# Microcontroller.net
KiCad netlist of a schematic drawn in Altium Designer
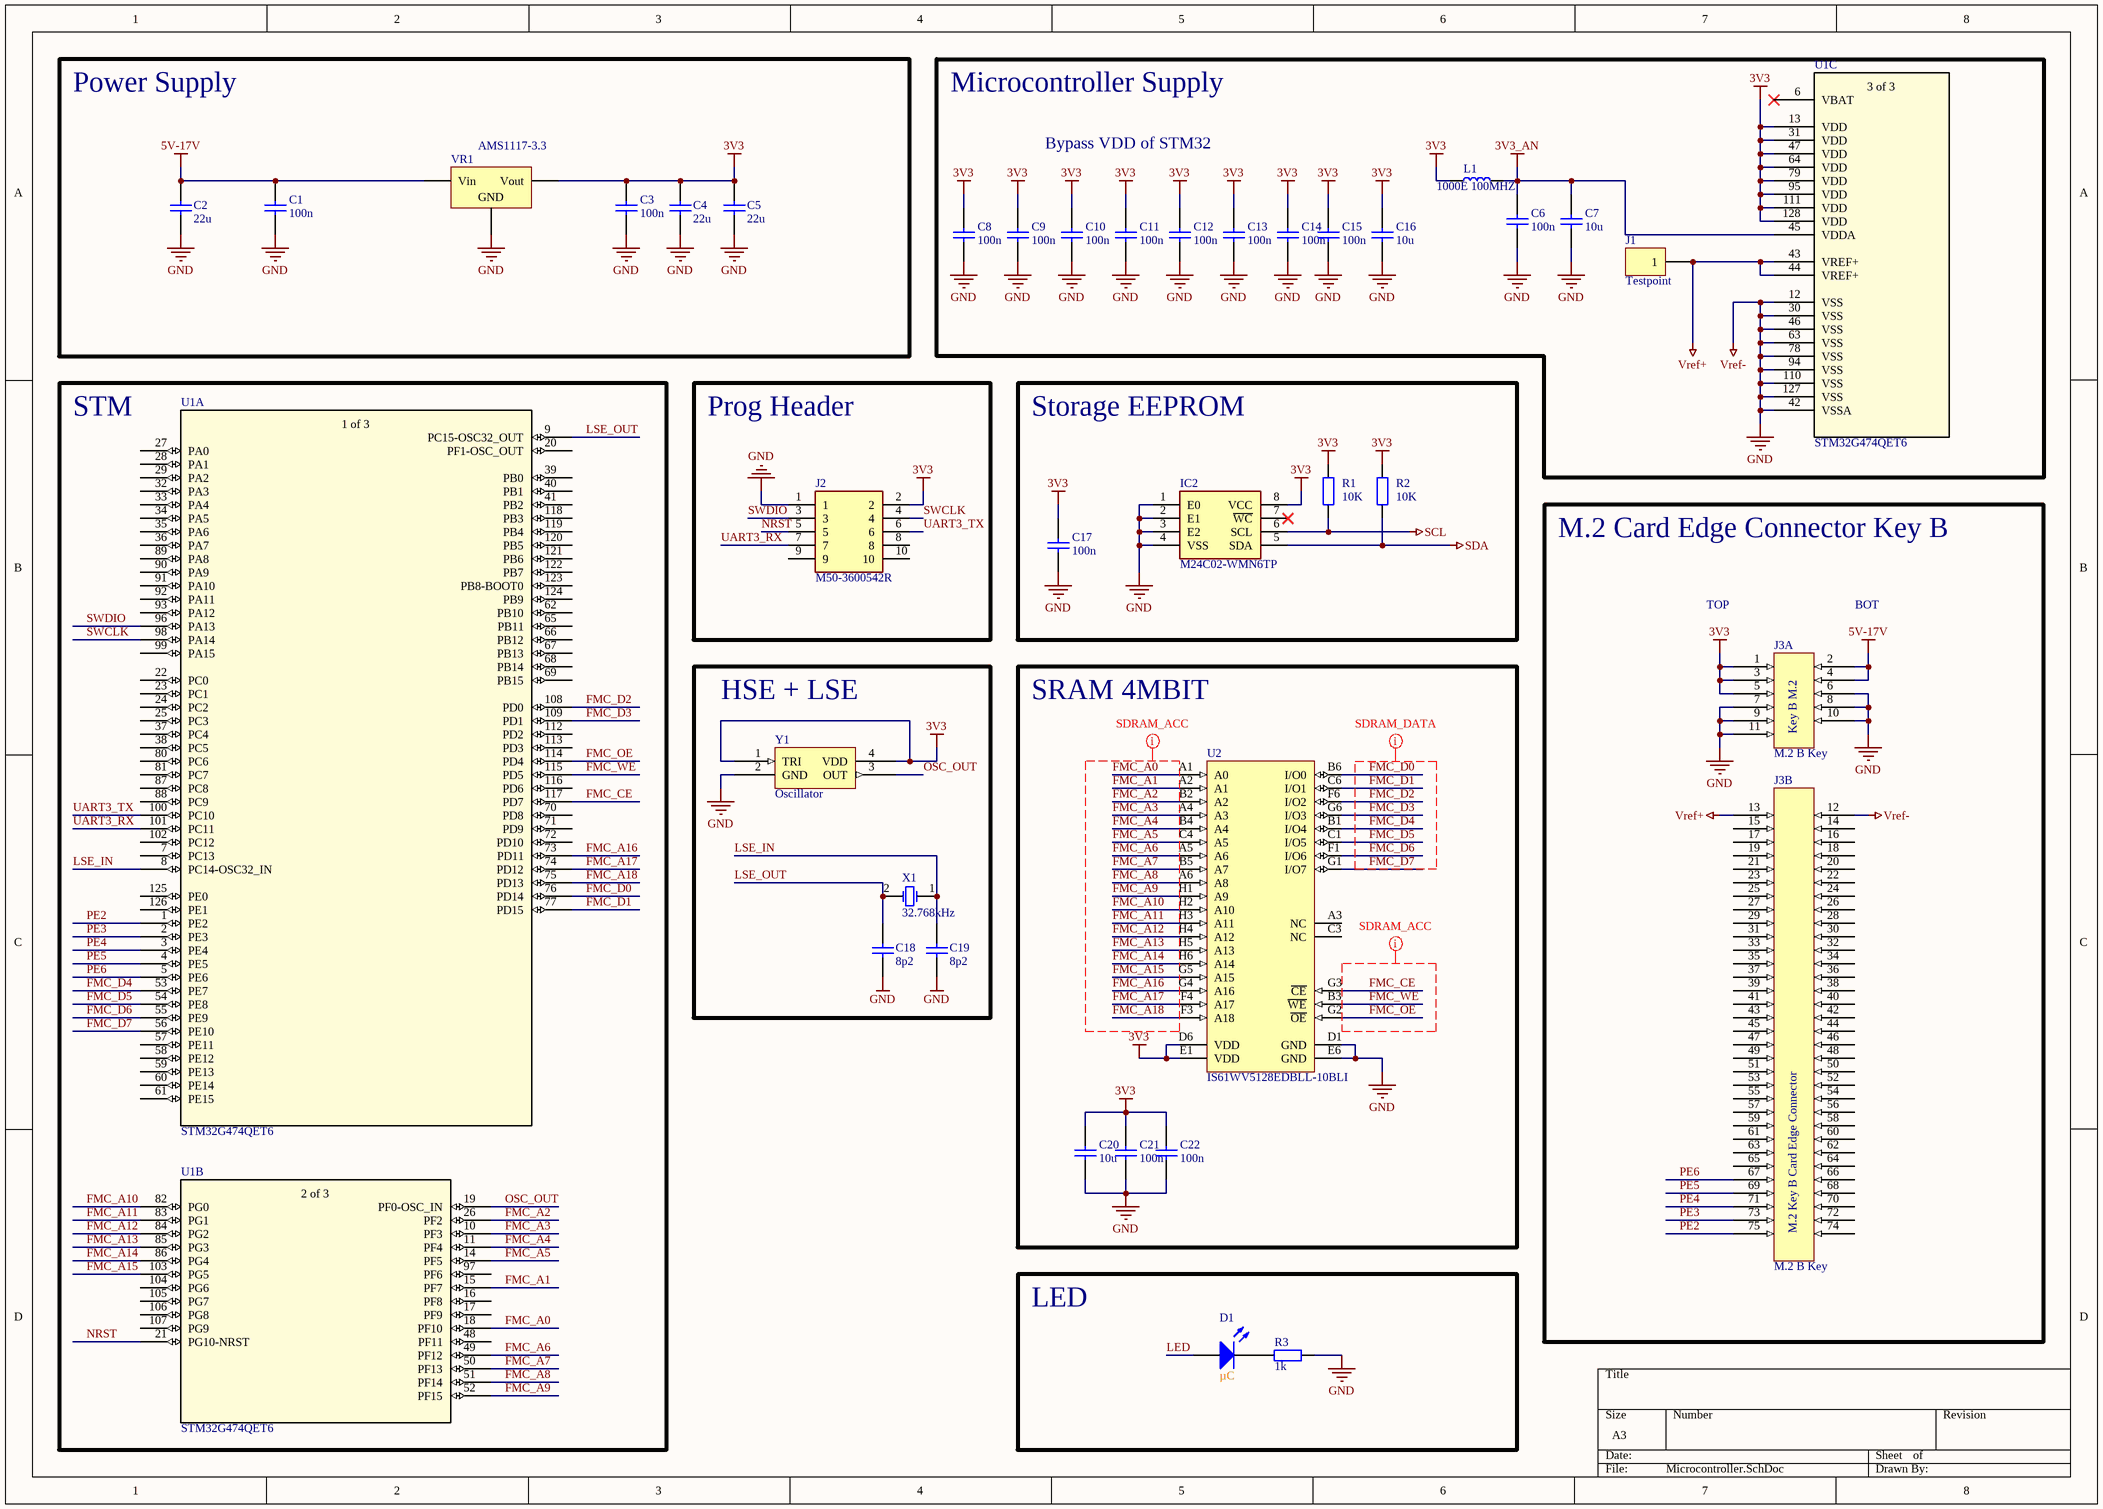
[diagram p0: Microcontroller.SchDoc]

(export (version "E")
  (design (tool "Eeschema 10.0.6"))
  (components
    (comp (ref "C1")
      (value "100n")
      (footprint "0402C")
      (description "Kondensator")
      (libsource (lib "WimLib") (part "Cap Ceramic"))
    )
    (comp (ref "C2")
      (value "22u")
      (footprint "1206C")
      (description "Kondensator")
      (libsource (lib "WimLib") (part "Cap Ceramic"))
    )
    (comp (ref "C3")
      (value "100n")
      (footprint "0402C")
      (description "Kondensator")
      (libsource (lib "WimLib") (part "Cap Ceramic"))
    )
    (comp (ref "C4")
      (value "22u")
      (footprint "1206C")
      (description "Kondensator")
      (libsource (lib "WimLib") (part "Cap Ceramic"))
    )
    (comp (ref "C5")
      (value "22u")
      (footprint "1206C")
      (description "Kondensator")
      (libsource (lib "WimLib") (part "Cap Ceramic"))
    )
    (comp (ref "C6")
      (value "100n")
      (footprint "0402C")
      (description "Kondensator")
      (libsource (lib "WimLib") (part "Cap Ceramic"))
    )
    (comp (ref "C7")
      (value "10u")
      (footprint "0603CH")
      (description "Kondensator")
      (libsource (lib "WimLib") (part "Cap Ceramic"))
    )
    (comp (ref "C8")
      (value "100n")
      (footprint "0402C")
      (description "Kondensator")
      (libsource (lib "WimLib") (part "Cap Ceramic"))
    )
    (comp (ref "C9")
      (value "100n")
      (footprint "0402C")
      (description "Kondensator")
      (libsource (lib "WimLib") (part "Cap Ceramic"))
    )
    (comp (ref "C10")
      (value "100n")
      (footprint "0402C")
      (description "Kondensator")
      (libsource (lib "WimLib") (part "Cap Ceramic"))
    )
    (comp (ref "C11")
      (value "100n")
      (footprint "0402C")
      (description "Kondensator")
      (libsource (lib "WimLib") (part "Cap Ceramic"))
    )
    (comp (ref "C12")
      (value "100n")
      (footprint "0402C")
      (description "Kondensator")
      (libsource (lib "WimLib") (part "Cap Ceramic"))
    )
    (comp (ref "C13")
      (value "100n")
      (footprint "0402C")
      (description "Kondensator")
      (libsource (lib "WimLib") (part "Cap Ceramic"))
    )
    (comp (ref "C14")
      (value "100n")
      (footprint "0402C")
      (description "Kondensator")
      (libsource (lib "WimLib") (part "Cap Ceramic"))
    )
    (comp (ref "C15")
      (value "100n")
      (footprint "0402C")
      (description "Kondensator")
      (libsource (lib "WimLib") (part "Cap Ceramic"))
    )
    (comp (ref "C16")
      (value "10u")
      (footprint "0603CH")
      (description "Kondensator")
      (libsource (lib "WimLib") (part "Cap Ceramic"))
    )
    (comp (ref "C17")
      (value "100n")
      (footprint "0402C")
      (description "Kondensator")
      (libsource (lib "WimLib") (part "Cap Ceramic"))
    )
    (comp (ref "C18")
      (value "8p2")
      (footprint "0402C")
      (description "Kondensator")
      (libsource (lib "WimLib") (part "Cap Ceramic"))
    )
    (comp (ref "C19")
      (value "8p2")
      (footprint "0402C")
      (description "Kondensator")
      (libsource (lib "WimLib") (part "Cap Ceramic"))
    )
    (comp (ref "C20")
      (value "10u")
      (footprint "0603CH")
      (description "Kondensator")
      (libsource (lib "WimLib") (part "Cap Ceramic"))
    )
    (comp (ref "C21")
      (value "100n")
      (footprint "0402C")
      (description "Kondensator")
      (libsource (lib "WimLib") (part "Cap Ceramic"))
    )
    (comp (ref "C22")
      (value "100n")
      (footprint "0402C")
      (description "Kondensator")
      (libsource (lib "WimLib") (part "Cap Ceramic"))
    )
    (comp (ref "D1")
      (value "µC")
      (footprint "1206_C")
      (description "Typical RED, GREEN, YELLOW, AMBER GaAs LED")
      (fields (field (name "PUBLISHER") "Altium Limited"))
      (libsource (lib "Miscellaneous Devices") (part "LED2"))
    )
    (comp (ref "IC2")
      (value "M24C02-WMN6TP")
      (footprint "SamacSys:SOIC127P600X175-8N")
      (description "Integrated Circuit")
      (fields (field (name "MOUSER PART NUMBER") "511-M24C02-WMN6TP"))
      (libsource (lib "SamacSys") (part "M24C02-WMN6TP"))
    )
    (comp (ref "J1")
      (value "Testpoint")
      (footprint "TESTPOINT")
      (description "Header, 1-Pin")
      (fields (field (name "PUBLISHER") "Altium Limited"))
      (libsource (lib "WimLibCon") (part "Header 1"))
    )
    (comp (ref "J2")
      (value "M50-3600542R")
      (footprint "SamacSys:HUSSP10W40P127_2X5_635X340X420P")
      (description "Connector")
      (fields (field (name "MOUSER PART NUMBER") "855-M50-3600542R"))
      (libsource (lib "*") (part "M50-3600542R"))
    )
    (comp (ref "J3")
      (value "M.2 B Key")
      (footprint "M.2 Key B")
      (libsource (lib "SimonLib") (part "M.2 B Key"))
    )
    (comp (ref "L1") (value "1000E 100MHZ") (footprint "0603L") (libsource (lib "WimLib") (part "Inductor")))
    (comp (ref "R1")
      (value "10K")
      (footprint "0402R")
      (description "Widerstand")
      (libsource (lib "WimLib") (part "Resistor"))
    )
    (comp (ref "R2")
      (value "10K")
      (footprint "0402R")
      (description "Widerstand")
      (libsource (lib "WimLib") (part "Resistor"))
    )
    (comp (ref "R3")
      (value "1k")
      (footprint "0402_R")
      (description "Resistor")
      (fields (field (name "Comment") "Res2") (field (name "PUBLISHER") "Altium Limited"))
      (libsource (lib "Miscellaneous Devices") (part "Res2"))
    )
    (comp (ref "U1")
      (value "STM32G474QET6")
      (footprint "LPQFP-128")
      (description "No Description Available")
      (libsource (lib "STM32G474QET6") (part "STM32G474QET6"))
    )
    (comp (ref "U2")
      (value "IS61WV5128EDBLL-10BLI")
      (footprint "ISSI-TF-BGA-36-6000x8000DE")
      (fields (field (name "MANUFACTURER") "Integrated Silicon Solution Inc (ISSI)"))
      (libsource (lib "Altium Content Vault") (part "ISSI-IS61WV5128EDBLL-TF-BGA-36"))
    )
    (comp (ref "VR1")
      (value "AMS1117-3.3")
      (footprint "SOT-223")
      (description "低压差线性稳压(LDO)")
      (libsource (lib "LDO") (part "SOT-223 AMS1117-3.3"))
    )
    (comp (ref "X1")
      (value "32.768kHz")
      (footprint "XTAL32768")
      (description "Crystal Oscillator")
      (fields (field (name "PUBLISHER") "Altium Limited"))
      (libsource (lib "WimLib") (part "XTAL"))
    )
    (comp (ref "Y1")
      (value "Oscillator")
      (footprint "Crystal SMD3225")
      (libsource (lib "SimonLib") (part "Oscillator"))
    )
  )
  (nets
    (net (code "1") (name "/FMC_A0") (class "Default")
      (node (ref "U1") (pin "18") (pinfunction "PF10_18") (pintype "bidirectional"))
      (node (ref "U2") (pin "A1") (pinfunction "A0_A1") (pintype "input"))
    )
    (net (code "2") (name "/FMC_A1") (class "Default")
      (node (ref "U1") (pin "15") (pinfunction "PF7_15") (pintype "bidirectional"))
      (node (ref "U2") (pin "A2") (pinfunction "A1_A2") (pintype "input"))
    )
    (net (code "3") (name "/FMC_A2") (class "Default")
      (node (ref "U1") (pin "26") (pinfunction "PF2_26") (pintype "bidirectional"))
      (node (ref "U2") (pin "B2") (pinfunction "A2_B2") (pintype "input"))
    )
    (net (code "4") (name "/FMC_A3") (class "Default")
      (node (ref "U1") (pin "10") (pinfunction "PF3_10") (pintype "bidirectional"))
      (node (ref "U2") (pin "A4") (pinfunction "A3_A4") (pintype "input"))
    )
    (net (code "5") (name "/FMC_A4") (class "Default")
      (node (ref "U1") (pin "11") (pinfunction "PF4_11") (pintype "bidirectional"))
      (node (ref "U2") (pin "B4") (pinfunction "A4_B4") (pintype "input"))
    )
    (net (code "6") (name "/FMC_A5") (class "Default")
      (node (ref "U1") (pin "14") (pinfunction "PF5_14") (pintype "bidirectional"))
      (node (ref "U2") (pin "C4") (pinfunction "A5_C4") (pintype "input"))
    )
    (net (code "7") (name "/FMC_A6") (class "Default")
      (node (ref "U1") (pin "49") (pinfunction "PF12_49") (pintype "bidirectional"))
      (node (ref "U2") (pin "A5") (pinfunction "A6_A5") (pintype "input"))
    )
    (net (code "8") (name "/FMC_A7") (class "Default")
      (node (ref "U1") (pin "50") (pinfunction "PF13_50") (pintype "bidirectional"))
      (node (ref "U2") (pin "B5") (pinfunction "A7_B5") (pintype "input"))
    )
    (net (code "9") (name "/FMC_A8") (class "Default")
      (node (ref "U1") (pin "51") (pinfunction "PF14_51") (pintype "bidirectional"))
      (node (ref "U2") (pin "A6") (pinfunction "A8_A6") (pintype "input"))
    )
    (net (code "10") (name "/FMC_A9") (class "Default")
      (node (ref "U1") (pin "52") (pinfunction "PF15_52") (pintype "bidirectional"))
      (node (ref "U2") (pin "H1") (pinfunction "A9_H1") (pintype "input"))
    )
    (net (code "11") (name "/FMC_A10") (class "Default")
      (node (ref "U1") (pin "82") (pinfunction "PG0_82") (pintype "bidirectional"))
      (node (ref "U2") (pin "H2") (pinfunction "A10_H2") (pintype "input"))
    )
    (net (code "12") (name "/FMC_A11") (class "Default")
      (node (ref "U1") (pin "83") (pinfunction "PG1_83") (pintype "bidirectional"))
      (node (ref "U2") (pin "H3") (pinfunction "A11_H3") (pintype "input"))
    )
    (net (code "13") (name "/FMC_A12") (class "Default")
      (node (ref "U1") (pin "84") (pinfunction "PG2_84") (pintype "bidirectional"))
      (node (ref "U2") (pin "H4") (pinfunction "A12_H4") (pintype "input"))
    )
    (net (code "14") (name "/FMC_A13") (class "Default")
      (node (ref "U1") (pin "85") (pinfunction "PG3_85") (pintype "bidirectional"))
      (node (ref "U2") (pin "H5") (pinfunction "A13_H5") (pintype "input"))
    )
    (net (code "15") (name "/FMC_A14") (class "Default")
      (node (ref "U1") (pin "86") (pinfunction "PG4_86") (pintype "bidirectional"))
      (node (ref "U2") (pin "H6") (pinfunction "A14_H6") (pintype "input"))
    )
    (net (code "16") (name "/FMC_A15") (class "Default")
      (node (ref "U1") (pin "103") (pinfunction "PG5_103") (pintype "bidirectional"))
      (node (ref "U2") (pin "G5") (pinfunction "A15_G5") (pintype "input"))
    )
    (net (code "17") (name "/FMC_A16") (class "Default")
      (node (ref "U1") (pin "73") (pinfunction "PD11_73") (pintype "bidirectional"))
      (node (ref "U2") (pin "G4") (pinfunction "A16_G4") (pintype "input"))
    )
    (net (code "18") (name "/FMC_A17") (class "Default")
      (node (ref "U1") (pin "74") (pinfunction "PD12_74") (pintype "bidirectional"))
      (node (ref "U2") (pin "F4") (pinfunction "A17_F4") (pintype "input"))
    )
    (net (code "19") (name "/FMC_A18") (class "Default")
      (node (ref "U1") (pin "75") (pinfunction "PD13_75") (pintype "bidirectional"))
      (node (ref "U2") (pin "F3") (pinfunction "A18_F3") (pintype "input"))
    )
    (net (code "20") (name "/FMC_CE") (class "Default")
      (node (ref "U1") (pin "117") (pinfunction "PD7_117") (pintype "bidirectional"))
      (node (ref "U2") (pin "G3") (pinfunction "~{CE}_G3") (pintype "input"))
    )
    (net (code "21") (name "/FMC_D0") (class "Default")
      (node (ref "U1") (pin "76") (pinfunction "PD14_76") (pintype "bidirectional"))
      (node (ref "U2") (pin "B6") (pinfunction "I/O0_B6") (pintype "bidirectional"))
    )
    (net (code "22") (name "/FMC_D1") (class "Default")
      (node (ref "U1") (pin "77") (pinfunction "PD15_77") (pintype "bidirectional"))
      (node (ref "U2") (pin "C6") (pinfunction "I/O1_C6") (pintype "bidirectional"))
    )
    (net (code "23") (name "/FMC_D2") (class "Default")
      (node (ref "U1") (pin "108") (pinfunction "PD0_108") (pintype "bidirectional"))
      (node (ref "U2") (pin "F6") (pinfunction "I/O2_F6") (pintype "bidirectional"))
    )
    (net (code "24") (name "/FMC_D3") (class "Default")
      (node (ref "U1") (pin "109") (pinfunction "PD1_109") (pintype "bidirectional"))
      (node (ref "U2") (pin "G6") (pinfunction "I/O3_G6") (pintype "bidirectional"))
    )
    (net (code "25") (name "/FMC_D4") (class "Default")
      (node (ref "U1") (pin "53") (pinfunction "PE7_53") (pintype "bidirectional"))
      (node (ref "U2") (pin "B1") (pinfunction "I/O4_B1") (pintype "bidirectional"))
    )
    (net (code "26") (name "/FMC_D5") (class "Default")
      (node (ref "U1") (pin "54") (pinfunction "PE8_54") (pintype "bidirectional"))
      (node (ref "U2") (pin "C1") (pinfunction "I/O5_C1") (pintype "bidirectional"))
    )
    (net (code "27") (name "/FMC_D6") (class "Default")
      (node (ref "U1") (pin "55") (pinfunction "PE9_55") (pintype "bidirectional"))
      (node (ref "U2") (pin "F1") (pinfunction "I/O6_F1") (pintype "bidirectional"))
    )
    (net (code "28") (name "/FMC_D7") (class "Default")
      (node (ref "U1") (pin "56") (pinfunction "PE10_56") (pintype "bidirectional"))
      (node (ref "U2") (pin "G1") (pinfunction "I/O7_G1") (pintype "bidirectional"))
    )
    (net (code "29") (name "/FMC_OE") (class "Default")
      (node (ref "U1") (pin "114") (pinfunction "PD4_114") (pintype "bidirectional"))
      (node (ref "U2") (pin "G2") (pinfunction "~{OE}_G2") (pintype "input"))
    )
    (net (code "30") (name "/FMC_WE") (class "Default")
      (node (ref "U1") (pin "115") (pinfunction "PD5_115") (pintype "bidirectional"))
      (node (ref "U2") (pin "B3") (pinfunction "~{WE}_B3") (pintype "input"))
    )
    (net (code "31") (name "/LED") (class "Default")
      (node (ref "D1") (pin "1") (pinfunction "A_1") (pintype "passive"))
    )
    (net (code "32") (name "/LSE_IN") (class "Default")
      (node (ref "C19") (pin "2") (pinfunction "2_2") (pintype "passive"))
      (node (ref "U1") (pin "8") (pinfunction "PC14-OSC32_IN_8") (pintype "bidirectional"))
      (node (ref "X1") (pin "1") (pinfunction "OSC1_1") (pintype "passive"))
    )
    (net (code "33") (name "/LSE_OUT") (class "Default")
      (node (ref "C18") (pin "2") (pinfunction "2_2") (pintype "passive"))
      (node (ref "U1") (pin "9") (pinfunction "PC15-OSC32_OUT_9") (pintype "bidirectional"))
      (node (ref "X1") (pin "2") (pinfunction "OSC2_2") (pintype "passive"))
    )
    (net (code "34") (name "/NRST") (class "Default")
      (node (ref "J2") (pin "5") (pinfunction "5_5") (pintype "passive"))
      (node (ref "U1") (pin "21") (pinfunction "PG10-NRST_21") (pintype "bidirectional"))
    )
    (net (code "35") (name "/OSC_OUT") (class "Default")
      (node (ref "U1") (pin "19") (pinfunction "PF0-OSC_IN_19") (pintype "bidirectional"))
      (node (ref "Y1") (pin "3") (pinfunction "OUT_3") (pintype "output"))
    )
    (net (code "36") (name "/PE2") (class "Default")
      (node (ref "J3") (pin "75") (pintype "input"))
      (node (ref "U1") (pin "1") (pinfunction "PE2_1") (pintype "bidirectional"))
    )
    (net (code "37") (name "/PE3") (class "Default")
      (node (ref "J3") (pin "73") (pintype "input"))
      (node (ref "U1") (pin "2") (pinfunction "PE3_2") (pintype "bidirectional"))
    )
    (net (code "38") (name "/PE4") (class "Default")
      (node (ref "J3") (pin "71") (pintype "input"))
      (node (ref "U1") (pin "3") (pinfunction "PE4_3") (pintype "bidirectional"))
    )
    (net (code "39") (name "/PE5") (class "Default")
      (node (ref "J3") (pin "69") (pintype "input"))
      (node (ref "U1") (pin "4") (pinfunction "PE5_4") (pintype "bidirectional"))
    )
    (net (code "40") (name "/PE6") (class "Default")
      (node (ref "J3") (pin "67") (pintype "input"))
      (node (ref "U1") (pin "5") (pinfunction "PE6_5") (pintype "bidirectional"))
    )
    (net (code "41") (name "/SWCLK") (class "Default")
      (node (ref "J2") (pin "4") (pinfunction "4_4") (pintype "passive"))
      (node (ref "U1") (pin "98") (pinfunction "PA14_98") (pintype "bidirectional"))
    )
    (net (code "42") (name "/SWDIO") (class "Default")
      (node (ref "J2") (pin "3") (pinfunction "3_3") (pintype "passive"))
      (node (ref "U1") (pin "96") (pinfunction "PA13_96") (pintype "bidirectional"))
    )
    (net (code "43") (name "/UART3_RX") (class "Default")
      (node (ref "J2") (pin "7") (pinfunction "7_7") (pintype "passive"))
      (node (ref "U1") (pin "101") (pinfunction "PC11_101") (pintype "bidirectional"))
    )
    (net (code "44") (name "/UART3_TX") (class "Default")
      (node (ref "J2") (pin "6") (pinfunction "6_6") (pintype "passive"))
      (node (ref "U1") (pin "100") (pinfunction "PC10_100") (pintype "bidirectional"))
    )
    (net (code "45") (name "3V3") (class "Default")
      (node (ref "C10") (pin "2") (pinfunction "2_2") (pintype "passive"))
      (node (ref "C11") (pin "2") (pinfunction "2_2") (pintype "passive"))
      (node (ref "C12") (pin "2") (pinfunction "2_2") (pintype "passive"))
      (node (ref "C13") (pin "2") (pinfunction "2_2") (pintype "passive"))
      (node (ref "C14") (pin "2") (pinfunction "2_2") (pintype "passive"))
      (node (ref "C15") (pin "2") (pinfunction "2_2") (pintype "passive"))
      (node (ref "C16") (pin "1") (pinfunction "1_1") (pintype "passive"))
      (node (ref "C17") (pin "2") (pinfunction "2_2") (pintype "passive"))
      (node (ref "C20") (pin "1") (pinfunction "1_1") (pintype "passive"))
      (node (ref "C21") (pin "2") (pinfunction "2_2") (pintype "passive"))
      (node (ref "C22") (pin "2") (pinfunction "2_2") (pintype "passive"))
      (node (ref "C3") (pin "2") (pinfunction "2_2") (pintype "passive"))
      (node (ref "C4") (pin "2") (pinfunction "2_2") (pintype "passive"))
      (node (ref "C5") (pin "2") (pinfunction "2_2") (pintype "passive"))
      (node (ref "C8") (pin "2") (pinfunction "2_2") (pintype "passive"))
      (node (ref "C9") (pin "2") (pinfunction "2_2") (pintype "passive"))
      (node (ref "IC2") (pin "8") (pinfunction "VCC_8") (pintype "passive"))
      (node (ref "J2") (pin "2") (pinfunction "2_2") (pintype "passive"))
      (node (ref "J3") (pin "1") (pintype "input"))
      (node (ref "J3") (pin "3") (pintype "input"))
      (node (ref "J3") (pin "5") (pintype "input"))
      (node (ref "L1") (pin "1") (pinfunction "1_1") (pintype "passive"))
      (node (ref "R1") (pin "1") (pinfunction "1_1") (pintype "passive"))
      (node (ref "R2") (pin "1") (pinfunction "1_1") (pintype "passive"))
      (node (ref "U1") (pin "111") (pinfunction "VDD_111") (pintype "power_in"))
      (node (ref "U1") (pin "128") (pinfunction "VDD_128") (pintype "power_in"))
      (node (ref "U1") (pin "13") (pinfunction "VDD_13") (pintype "power_in"))
      (node (ref "U1") (pin "31") (pinfunction "VDD_31") (pintype "power_in"))
      (node (ref "U1") (pin "47") (pinfunction "VDD_47") (pintype "power_in"))
      (node (ref "U1") (pin "64") (pinfunction "VDD_64") (pintype "power_in"))
      (node (ref "U1") (pin "79") (pinfunction "VDD_79") (pintype "power_in"))
      (node (ref "U1") (pin "95") (pinfunction "VDD_95") (pintype "power_in"))
      (node (ref "U2") (pin "D6") (pinfunction "VDD_D6") (pintype "power_in"))
      (node (ref "U2") (pin "E1") (pinfunction "VDD_E1") (pintype "power_in"))
      (node (ref "VR1") (pin "2") (pinfunction "Vout_2") (pintype "passive"))
      (node (ref "Y1") (pin "1") (pinfunction "TRI_1") (pintype "input"))
      (node (ref "Y1") (pin "4") (pinfunction "VDD_4") (pintype "power_in"))
    )
    (net (code "46") (name "3V3_AN") (class "Default")
      (node (ref "C6") (pin "2") (pinfunction "2_2") (pintype "passive"))
      (node (ref "C7") (pin "1") (pinfunction "1_1") (pintype "passive"))
      (node (ref "L1") (pin "2") (pinfunction "2_2") (pintype "passive"))
      (node (ref "U1") (pin "45") (pinfunction "VDDA_45") (pintype "power_in"))
    )
    (net (code "47") (name "5V-17V") (class "Default")
      (node (ref "C1") (pin "2") (pinfunction "2_2") (pintype "passive"))
      (node (ref "C2") (pin "2") (pinfunction "2_2") (pintype "passive"))
      (node (ref "J3") (pin "2") (pintype "input"))
      (node (ref "J3") (pin "4") (pintype "input"))
      (node (ref "VR1") (pin "3") (pinfunction "Vin_3") (pintype "passive"))
    )
    (net (code "48") (name "GND") (class "Default")
      (node (ref "C1") (pin "1") (pinfunction "1_1") (pintype "passive"))
      (node (ref "C10") (pin "1") (pinfunction "1_1") (pintype "passive"))
      (node (ref "C11") (pin "1") (pinfunction "1_1") (pintype "passive"))
      (node (ref "C12") (pin "1") (pinfunction "1_1") (pintype "passive"))
      (node (ref "C13") (pin "1") (pinfunction "1_1") (pintype "passive"))
      (node (ref "C14") (pin "1") (pinfunction "1_1") (pintype "passive"))
      (node (ref "C15") (pin "1") (pinfunction "1_1") (pintype "passive"))
      (node (ref "C16") (pin "2") (pinfunction "2_2") (pintype "passive"))
      (node (ref "C17") (pin "1") (pinfunction "1_1") (pintype "passive"))
      (node (ref "C18") (pin "1") (pinfunction "1_1") (pintype "passive"))
      (node (ref "C19") (pin "1") (pinfunction "1_1") (pintype "passive"))
      (node (ref "C2") (pin "1") (pinfunction "1_1") (pintype "passive"))
      (node (ref "C20") (pin "2") (pinfunction "2_2") (pintype "passive"))
      (node (ref "C21") (pin "1") (pinfunction "1_1") (pintype "passive"))
      (node (ref "C22") (pin "1") (pinfunction "1_1") (pintype "passive"))
      (node (ref "C3") (pin "1") (pinfunction "1_1") (pintype "passive"))
      (node (ref "C4") (pin "1") (pinfunction "1_1") (pintype "passive"))
      (node (ref "C5") (pin "1") (pinfunction "1_1") (pintype "passive"))
      (node (ref "C6") (pin "1") (pinfunction "1_1") (pintype "passive"))
      (node (ref "C7") (pin "2") (pinfunction "2_2") (pintype "passive"))
      (node (ref "C8") (pin "1") (pinfunction "1_1") (pintype "passive"))
      (node (ref "C9") (pin "1") (pinfunction "1_1") (pintype "passive"))
      (node (ref "IC2") (pin "1") (pinfunction "E0_1") (pintype "passive"))
      (node (ref "IC2") (pin "2") (pinfunction "E1_2") (pintype "passive"))
      (node (ref "IC2") (pin "3") (pinfunction "E2_3") (pintype "passive"))
      (node (ref "IC2") (pin "4") (pinfunction "VSS_4") (pintype "passive"))
      (node (ref "J2") (pin "1") (pinfunction "1_1") (pintype "passive"))
      (node (ref "J3") (pin "10") (pintype "input"))
      (node (ref "J3") (pin "11") (pintype "input"))
      (node (ref "J3") (pin "12") (pintype "input"))
      (node (ref "J3") (pin "6") (pintype "input"))
      (node (ref "J3") (pin "7") (pintype "input"))
      (node (ref "J3") (pin "8") (pintype "input"))
      (node (ref "J3") (pin "9") (pintype "input"))
      (node (ref "R3") (pin "1") (pinfunction "1_1") (pintype "passive"))
      (node (ref "U1") (pin "110") (pinfunction "VSS_110") (pintype "power_in"))
      (node (ref "U1") (pin "12") (pinfunction "VSS_12") (pintype "power_in"))
      (node (ref "U1") (pin "127") (pinfunction "VSS_127") (pintype "power_in"))
      (node (ref "U1") (pin "30") (pinfunction "VSS_30") (pintype "power_in"))
      (node (ref "U1") (pin "42") (pinfunction "VSSA_42") (pintype "power_in"))
      (node (ref "U1") (pin "46") (pinfunction "VSS_46") (pintype "power_in"))
      (node (ref "U1") (pin "63") (pinfunction "VSS_63") (pintype "power_in"))
      (node (ref "U1") (pin "78") (pinfunction "VSS_78") (pintype "power_in"))
      (node (ref "U1") (pin "94") (pinfunction "VSS_94") (pintype "power_in"))
      (node (ref "U2") (pin "D1") (pinfunction "GND_D1") (pintype "power_in"))
      (node (ref "U2") (pin "E6") (pinfunction "GND_E6") (pintype "power_in"))
      (node (ref "VR1") (pin "1") (pinfunction "GND_1") (pintype "passive"))
      (node (ref "Y1") (pin "2") (pinfunction "GND_2") (pintype "power_in"))
    )
    (net (code "49") (name "Net-(D1-K)") (class "Default")
      (node (ref "D1") (pin "2") (pinfunction "K_2") (pintype "passive"))
      (node (ref "R3") (pin "2") (pinfunction "2_2") (pintype "passive"))
    )
    (net (code "50") (name "SCL") (class "Default")
      (node (ref "IC2") (pin "6") (pinfunction "SCL_6") (pintype "passive"))
      (node (ref "R1") (pin "2") (pinfunction "2_2") (pintype "passive"))
    )
    (net (code "51") (name "SDA") (class "Default")
      (node (ref "IC2") (pin "5") (pinfunction "SDA_5") (pintype "passive"))
      (node (ref "R2") (pin "2") (pinfunction "2_2") (pintype "passive"))
    )
    (net (code "52") (name "Vref+") (class "Default")
      (node (ref "J1") (pin "1") (pinfunction "1_1") (pintype "passive"))
      (node (ref "J3") (pin "13") (pintype "input"))
      (node (ref "U1") (pin "43") (pinfunction "VREF+_43") (pintype "power_in"))
      (node (ref "U1") (pin "44") (pinfunction "VREF+_44") (pintype "power_in"))
    )
    (net (code "53") (name "unconnected-(IC2-~{WC}-Pad7)") (class "Default")
      (node (ref "IC2") (pin "7") (pinfunction "~{WC}_7") (pintype "passive+no_connect"))
    )
    (net (code "54") (name "unconnected-(J2-Pad8)") (class "Default")
      (node (ref "J2") (pin "8") (pinfunction "8_8") (pintype "passive"))
    )
    (net (code "55") (name "unconnected-(J2-Pad9)") (class "Default")
      (node (ref "J2") (pin "9") (pinfunction "9_9") (pintype "passive"))
    )
    (net (code "56") (name "unconnected-(J2-Pad10)") (class "Default")
      (node (ref "J2") (pin "10") (pinfunction "10_10") (pintype "passive"))
    )
    (net (code "57") (name "unconnected-(J3-Pad14)") (class "Default")
      (node (ref "J3") (pin "14") (pintype "input"))
    )
    (net (code "58") (name "unconnected-(J3-Pad15)") (class "Default")
      (node (ref "J3") (pin "15") (pintype "input"))
    )
    (net (code "59") (name "unconnected-(J3-Pad16)") (class "Default")
      (node (ref "J3") (pin "16") (pintype "input"))
    )
    (net (code "60") (name "unconnected-(J3-Pad17)") (class "Default")
      (node (ref "J3") (pin "17") (pintype "input"))
    )
    (net (code "61") (name "unconnected-(J3-Pad18)") (class "Default")
      (node (ref "J3") (pin "18") (pintype "input"))
    )
    (net (code "62") (name "unconnected-(J3-Pad19)") (class "Default")
      (node (ref "J3") (pin "19") (pintype "input"))
    )
    (net (code "63") (name "unconnected-(J3-Pad20)") (class "Default")
      (node (ref "J3") (pin "20") (pintype "input"))
    )
    (net (code "64") (name "unconnected-(J3-Pad21)") (class "Default")
      (node (ref "J3") (pin "21") (pintype "input"))
    )
    (net (code "65") (name "unconnected-(J3-Pad22)") (class "Default")
      (node (ref "J3") (pin "22") (pintype "input"))
    )
    (net (code "66") (name "unconnected-(J3-Pad23)") (class "Default")
      (node (ref "J3") (pin "23") (pintype "input"))
    )
    (net (code "67") (name "unconnected-(J3-Pad24)") (class "Default")
      (node (ref "J3") (pin "24") (pintype "input"))
    )
    (net (code "68") (name "unconnected-(J3-Pad25)") (class "Default")
      (node (ref "J3") (pin "25") (pintype "input"))
    )
    (net (code "69") (name "unconnected-(J3-Pad26)") (class "Default")
      (node (ref "J3") (pin "26") (pintype "input"))
    )
    (net (code "70") (name "unconnected-(J3-Pad27)") (class "Default")
      (node (ref "J3") (pin "27") (pintype "input"))
    )
    (net (code "71") (name "unconnected-(J3-Pad28)") (class "Default")
      (node (ref "J3") (pin "28") (pintype "input"))
    )
    (net (code "72") (name "unconnected-(J3-Pad29)") (class "Default")
      (node (ref "J3") (pin "29") (pintype "input"))
    )
    (net (code "73") (name "unconnected-(J3-Pad30)") (class "Default")
      (node (ref "J3") (pin "30") (pintype "input"))
    )
    (net (code "74") (name "unconnected-(J3-Pad31)") (class "Default")
      (node (ref "J3") (pin "31") (pintype "input"))
    )
    (net (code "75") (name "unconnected-(J3-Pad32)") (class "Default")
      (node (ref "J3") (pin "32") (pintype "input"))
    )
    (net (code "76") (name "unconnected-(J3-Pad33)") (class "Default")
      (node (ref "J3") (pin "33") (pintype "input"))
    )
    (net (code "77") (name "unconnected-(J3-Pad34)") (class "Default")
      (node (ref "J3") (pin "34") (pintype "input"))
    )
    (net (code "78") (name "unconnected-(J3-Pad35)") (class "Default")
      (node (ref "J3") (pin "35") (pintype "input"))
    )
    (net (code "79") (name "unconnected-(J3-Pad36)") (class "Default")
      (node (ref "J3") (pin "36") (pintype "input"))
    )
    (net (code "80") (name "unconnected-(J3-Pad37)") (class "Default")
      (node (ref "J3") (pin "37") (pintype "input"))
    )
    (net (code "81") (name "unconnected-(J3-Pad38)") (class "Default")
      (node (ref "J3") (pin "38") (pintype "input"))
    )
    (net (code "82") (name "unconnected-(J3-Pad39)") (class "Default")
      (node (ref "J3") (pin "39") (pintype "input"))
    )
    (net (code "83") (name "unconnected-(J3-Pad40)") (class "Default")
      (node (ref "J3") (pin "40") (pintype "input"))
    )
    (net (code "84") (name "unconnected-(J3-Pad41)") (class "Default")
      (node (ref "J3") (pin "41") (pintype "input"))
    )
    (net (code "85") (name "unconnected-(J3-Pad42)") (class "Default")
      (node (ref "J3") (pin "42") (pintype "input"))
    )
    (net (code "86") (name "unconnected-(J3-Pad43)") (class "Default")
      (node (ref "J3") (pin "43") (pintype "input"))
    )
    (net (code "87") (name "unconnected-(J3-Pad44)") (class "Default")
      (node (ref "J3") (pin "44") (pintype "input"))
    )
    (net (code "88") (name "unconnected-(J3-Pad45)") (class "Default")
      (node (ref "J3") (pin "45") (pintype "input"))
    )
    (net (code "89") (name "unconnected-(J3-Pad46)") (class "Default")
      (node (ref "J3") (pin "46") (pintype "input"))
    )
    (net (code "90") (name "unconnected-(J3-Pad47)") (class "Default")
      (node (ref "J3") (pin "47") (pintype "input"))
    )
    (net (code "91") (name "unconnected-(J3-Pad48)") (class "Default")
      (node (ref "J3") (pin "48") (pintype "input"))
    )
    (net (code "92") (name "unconnected-(J3-Pad49)") (class "Default")
      (node (ref "J3") (pin "49") (pintype "input"))
    )
    (net (code "93") (name "unconnected-(J3-Pad50)") (class "Default")
      (node (ref "J3") (pin "50") (pintype "input"))
    )
    (net (code "94") (name "unconnected-(J3-Pad51)") (class "Default")
      (node (ref "J3") (pin "51") (pintype "input"))
    )
    (net (code "95") (name "unconnected-(J3-Pad52)") (class "Default")
      (node (ref "J3") (pin "52") (pintype "input"))
    )
    (net (code "96") (name "unconnected-(J3-Pad53)") (class "Default")
      (node (ref "J3") (pin "53") (pintype "input"))
    )
    (net (code "97") (name "unconnected-(J3-Pad54)") (class "Default")
      (node (ref "J3") (pin "54") (pintype "input"))
    )
    (net (code "98") (name "unconnected-(J3-Pad55)") (class "Default")
      (node (ref "J3") (pin "55") (pintype "input"))
    )
    (net (code "99") (name "unconnected-(J3-Pad56)") (class "Default")
      (node (ref "J3") (pin "56") (pintype "input"))
    )
    (net (code "100") (name "unconnected-(J3-Pad57)") (class "Default")
      (node (ref "J3") (pin "57") (pintype "input"))
    )
    (net (code "101") (name "unconnected-(J3-Pad58)") (class "Default")
      (node (ref "J3") (pin "58") (pintype "input"))
    )
    (net (code "102") (name "unconnected-(J3-Pad59)") (class "Default")
      (node (ref "J3") (pin "59") (pintype "input"))
    )
    (net (code "103") (name "unconnected-(J3-Pad60)") (class "Default")
      (node (ref "J3") (pin "60") (pintype "input"))
    )
    (net (code "104") (name "unconnected-(J3-Pad61)") (class "Default")
      (node (ref "J3") (pin "61") (pintype "input"))
    )
    (net (code "105") (name "unconnected-(J3-Pad62)") (class "Default")
      (node (ref "J3") (pin "62") (pintype "input"))
    )
    (net (code "106") (name "unconnected-(J3-Pad63)") (class "Default")
      (node (ref "J3") (pin "63") (pintype "input"))
    )
    (net (code "107") (name "unconnected-(J3-Pad64)") (class "Default")
      (node (ref "J3") (pin "64") (pintype "input"))
    )
    (net (code "108") (name "unconnected-(J3-Pad65)") (class "Default")
      (node (ref "J3") (pin "65") (pintype "input"))
    )
    (net (code "109") (name "unconnected-(J3-Pad66)") (class "Default")
      (node (ref "J3") (pin "66") (pintype "input"))
    )
    (net (code "110") (name "unconnected-(J3-Pad68)") (class "Default")
      (node (ref "J3") (pin "68") (pintype "input"))
    )
    (net (code "111") (name "unconnected-(J3-Pad70)") (class "Default")
      (node (ref "J3") (pin "70") (pintype "input"))
    )
    (net (code "112") (name "unconnected-(J3-Pad72)") (class "Default")
      (node (ref "J3") (pin "72") (pintype "input"))
    )
    (net (code "113") (name "unconnected-(J3-Pad74)") (class "Default")
      (node (ref "J3") (pin "74") (pintype "input"))
    )
    (net (code "114") (name "unconnected-(U1A-PA0-Pad27)") (class "Default")
      (node (ref "U1") (pin "27") (pinfunction "PA0_27") (pintype "bidirectional"))
    )
    (net (code "115") (name "unconnected-(U1A-PA1-Pad28)") (class "Default")
      (node (ref "U1") (pin "28") (pinfunction "PA1_28") (pintype "bidirectional"))
    )
    (net (code "116") (name "unconnected-(U1A-PA2-Pad29)") (class "Default")
      (node (ref "U1") (pin "29") (pinfunction "PA2_29") (pintype "bidirectional"))
    )
    (net (code "117") (name "unconnected-(U1A-PA3-Pad32)") (class "Default")
      (node (ref "U1") (pin "32") (pinfunction "PA3_32") (pintype "bidirectional"))
    )
    (net (code "118") (name "unconnected-(U1A-PA4-Pad33)") (class "Default")
      (node (ref "U1") (pin "33") (pinfunction "PA4_33") (pintype "bidirectional"))
    )
    (net (code "119") (name "unconnected-(U1A-PA5-Pad34)") (class "Default")
      (node (ref "U1") (pin "34") (pinfunction "PA5_34") (pintype "bidirectional"))
    )
    (net (code "120") (name "unconnected-(U1A-PA6-Pad35)") (class "Default")
      (node (ref "U1") (pin "35") (pinfunction "PA6_35") (pintype "bidirectional"))
    )
    (net (code "121") (name "unconnected-(U1A-PA7-Pad36)") (class "Default")
      (node (ref "U1") (pin "36") (pinfunction "PA7_36") (pintype "bidirectional"))
    )
    (net (code "122") (name "unconnected-(U1A-PA8-Pad89)") (class "Default")
      (node (ref "U1") (pin "89") (pinfunction "PA8_89") (pintype "bidirectional"))
    )
    (net (code "123") (name "unconnected-(U1A-PA9-Pad90)") (class "Default")
      (node (ref "U1") (pin "90") (pinfunction "PA9_90") (pintype "bidirectional"))
    )
    (net (code "124") (name "unconnected-(U1A-PA10-Pad91)") (class "Default")
      (node (ref "U1") (pin "91") (pinfunction "PA10_91") (pintype "bidirectional"))
    )
    (net (code "125") (name "unconnected-(U1A-PA11-Pad92)") (class "Default")
      (node (ref "U1") (pin "92") (pinfunction "PA11_92") (pintype "bidirectional"))
    )
    (net (code "126") (name "unconnected-(U1A-PA12-Pad93)") (class "Default")
      (node (ref "U1") (pin "93") (pinfunction "PA12_93") (pintype "bidirectional"))
    )
    (net (code "127") (name "unconnected-(U1A-PA15-Pad99)") (class "Default")
      (node (ref "U1") (pin "99") (pinfunction "PA15_99") (pintype "bidirectional"))
    )
    (net (code "128") (name "unconnected-(U1A-PB0-Pad39)") (class "Default")
      (node (ref "U1") (pin "39") (pinfunction "PB0_39") (pintype "bidirectional"))
    )
    (net (code "129") (name "unconnected-(U1A-PB1-Pad40)") (class "Default")
      (node (ref "U1") (pin "40") (pinfunction "PB1_40") (pintype "bidirectional"))
    )
    (net (code "130") (name "unconnected-(U1A-PB2-Pad41)") (class "Default")
      (node (ref "U1") (pin "41") (pinfunction "PB2_41") (pintype "bidirectional"))
    )
    (net (code "131") (name "unconnected-(U1A-PB3-Pad118)") (class "Default")
      (node (ref "U1") (pin "118") (pinfunction "PB3_118") (pintype "bidirectional"))
    )
    (net (code "132") (name "unconnected-(U1A-PB4-Pad119)") (class "Default")
      (node (ref "U1") (pin "119") (pinfunction "PB4_119") (pintype "bidirectional"))
    )
    (net (code "133") (name "unconnected-(U1A-PB5-Pad120)") (class "Default")
      (node (ref "U1") (pin "120") (pinfunction "PB5_120") (pintype "bidirectional"))
    )
    (net (code "134") (name "unconnected-(U1A-PB6-Pad121)") (class "Default")
      (node (ref "U1") (pin "121") (pinfunction "PB6_121") (pintype "bidirectional"))
    )
    (net (code "135") (name "unconnected-(U1A-PB7-Pad122)") (class "Default")
      (node (ref "U1") (pin "122") (pinfunction "PB7_122") (pintype "bidirectional"))
    )
    (net (code "136") (name "unconnected-(U1A-PB8-BOOT0-Pad123)") (class "Default")
      (node (ref "U1") (pin "123") (pinfunction "PB8-BOOT0_123") (pintype "bidirectional"))
    )
    (net (code "137") (name "unconnected-(U1A-PB9-Pad124)") (class "Default")
      (node (ref "U1") (pin "124") (pinfunction "PB9_124") (pintype "bidirectional"))
    )
    (net (code "138") (name "unconnected-(U1A-PB10-Pad62)") (class "Default")
      (node (ref "U1") (pin "62") (pinfunction "PB10_62") (pintype "bidirectional"))
    )
    (net (code "139") (name "unconnected-(U1A-PB11-Pad65)") (class "Default")
      (node (ref "U1") (pin "65") (pinfunction "PB11_65") (pintype "bidirectional"))
    )
    (net (code "140") (name "unconnected-(U1A-PB12-Pad66)") (class "Default")
      (node (ref "U1") (pin "66") (pinfunction "PB12_66") (pintype "bidirectional"))
    )
    (net (code "141") (name "unconnected-(U1A-PB13-Pad67)") (class "Default")
      (node (ref "U1") (pin "67") (pinfunction "PB13_67") (pintype "bidirectional"))
    )
    (net (code "142") (name "unconnected-(U1A-PB14-Pad68)") (class "Default")
      (node (ref "U1") (pin "68") (pinfunction "PB14_68") (pintype "bidirectional"))
    )
    (net (code "143") (name "unconnected-(U1A-PB15-Pad69)") (class "Default")
      (node (ref "U1") (pin "69") (pinfunction "PB15_69") (pintype "bidirectional"))
    )
    (net (code "144") (name "unconnected-(U1A-PC0-Pad22)") (class "Default")
      (node (ref "U1") (pin "22") (pinfunction "PC0_22") (pintype "bidirectional"))
    )
    (net (code "145") (name "unconnected-(U1A-PC1-Pad23)") (class "Default")
      (node (ref "U1") (pin "23") (pinfunction "PC1_23") (pintype "bidirectional"))
    )
    (net (code "146") (name "unconnected-(U1A-PC2-Pad24)") (class "Default")
      (node (ref "U1") (pin "24") (pinfunction "PC2_24") (pintype "bidirectional"))
    )
    (net (code "147") (name "unconnected-(U1A-PC3-Pad25)") (class "Default")
      (node (ref "U1") (pin "25") (pinfunction "PC3_25") (pintype "bidirectional"))
    )
    (net (code "148") (name "unconnected-(U1A-PC4-Pad37)") (class "Default")
      (node (ref "U1") (pin "37") (pinfunction "PC4_37") (pintype "bidirectional"))
    )
    (net (code "149") (name "unconnected-(U1A-PC5-Pad38)") (class "Default")
      (node (ref "U1") (pin "38") (pinfunction "PC5_38") (pintype "bidirectional"))
    )
    (net (code "150") (name "unconnected-(U1A-PC6-Pad80)") (class "Default")
      (node (ref "U1") (pin "80") (pinfunction "PC6_80") (pintype "bidirectional"))
    )
    (net (code "151") (name "unconnected-(U1A-PC7-Pad81)") (class "Default")
      (node (ref "U1") (pin "81") (pinfunction "PC7_81") (pintype "bidirectional"))
    )
    (net (code "152") (name "unconnected-(U1A-PC8-Pad87)") (class "Default")
      (node (ref "U1") (pin "87") (pinfunction "PC8_87") (pintype "bidirectional"))
    )
    (net (code "153") (name "unconnected-(U1A-PC9-Pad88)") (class "Default")
      (node (ref "U1") (pin "88") (pinfunction "PC9_88") (pintype "bidirectional"))
    )
    (net (code "154") (name "unconnected-(U1A-PC12-Pad102)") (class "Default")
      (node (ref "U1") (pin "102") (pinfunction "PC12_102") (pintype "bidirectional"))
    )
    (net (code "155") (name "unconnected-(U1A-PC13-Pad7)") (class "Default")
      (node (ref "U1") (pin "7") (pinfunction "PC13_7") (pintype "bidirectional"))
    )
    (net (code "156") (name "unconnected-(U1A-PD2-Pad112)") (class "Default")
      (node (ref "U1") (pin "112") (pinfunction "PD2_112") (pintype "bidirectional"))
    )
    (net (code "157") (name "unconnected-(U1A-PD3-Pad113)") (class "Default")
      (node (ref "U1") (pin "113") (pinfunction "PD3_113") (pintype "bidirectional"))
    )
    (net (code "158") (name "unconnected-(U1A-PD6-Pad116)") (class "Default")
      (node (ref "U1") (pin "116") (pinfunction "PD6_116") (pintype "bidirectional"))
    )
    (net (code "159") (name "unconnected-(U1A-PD8-Pad70)") (class "Default")
      (node (ref "U1") (pin "70") (pinfunction "PD8_70") (pintype "bidirectional"))
    )
    (net (code "160") (name "unconnected-(U1A-PD9-Pad71)") (class "Default")
      (node (ref "U1") (pin "71") (pinfunction "PD9_71") (pintype "bidirectional"))
    )
    (net (code "161") (name "unconnected-(U1A-PD10-Pad72)") (class "Default")
      (node (ref "U1") (pin "72") (pinfunction "PD10_72") (pintype "bidirectional"))
    )
    (net (code "162") (name "unconnected-(U1A-PE0-Pad125)") (class "Default")
      (node (ref "U1") (pin "125") (pinfunction "PE0_125") (pintype "bidirectional"))
    )
    (net (code "163") (name "unconnected-(U1A-PE1-Pad126)") (class "Default")
      (node (ref "U1") (pin "126") (pinfunction "PE1_126") (pintype "bidirectional"))
    )
    (net (code "164") (name "unconnected-(U1A-PE11-Pad57)") (class "Default")
      (node (ref "U1") (pin "57") (pinfunction "PE11_57") (pintype "bidirectional"))
    )
    (net (code "165") (name "unconnected-(U1A-PE12-Pad58)") (class "Default")
      (node (ref "U1") (pin "58") (pinfunction "PE12_58") (pintype "bidirectional"))
    )
    (net (code "166") (name "unconnected-(U1A-PE13-Pad59)") (class "Default")
      (node (ref "U1") (pin "59") (pinfunction "PE13_59") (pintype "bidirectional"))
    )
    (net (code "167") (name "unconnected-(U1A-PE14-Pad60)") (class "Default")
      (node (ref "U1") (pin "60") (pinfunction "PE14_60") (pintype "bidirectional"))
    )
    (net (code "168") (name "unconnected-(U1A-PE15-Pad61)") (class "Default")
      (node (ref "U1") (pin "61") (pinfunction "PE15_61") (pintype "bidirectional"))
    )
    (net (code "169") (name "unconnected-(U1A-PF1-OSC_OUT-Pad20)") (class "Default")
      (node (ref "U1") (pin "20") (pinfunction "PF1-OSC_OUT_20") (pintype "bidirectional"))
    )
    (net (code "170") (name "unconnected-(U1B-PF6-Pad97)") (class "Default")
      (node (ref "U1") (pin "97") (pinfunction "PF6_97") (pintype "bidirectional"))
    )
    (net (code "171") (name "unconnected-(U1B-PF8-Pad16)") (class "Default")
      (node (ref "U1") (pin "16") (pinfunction "PF8_16") (pintype "bidirectional"))
    )
    (net (code "172") (name "unconnected-(U1B-PF9-Pad17)") (class "Default")
      (node (ref "U1") (pin "17") (pinfunction "PF9_17") (pintype "bidirectional"))
    )
    (net (code "173") (name "unconnected-(U1B-PF11-Pad48)") (class "Default")
      (node (ref "U1") (pin "48") (pinfunction "PF11_48") (pintype "bidirectional"))
    )
    (net (code "174") (name "unconnected-(U1B-PG6-Pad104)") (class "Default")
      (node (ref "U1") (pin "104") (pinfunction "PG6_104") (pintype "bidirectional"))
    )
    (net (code "175") (name "unconnected-(U1B-PG7-Pad105)") (class "Default")
      (node (ref "U1") (pin "105") (pinfunction "PG7_105") (pintype "bidirectional"))
    )
    (net (code "176") (name "unconnected-(U1B-PG8-Pad106)") (class "Default")
      (node (ref "U1") (pin "106") (pinfunction "PG8_106") (pintype "bidirectional"))
    )
    (net (code "177") (name "unconnected-(U1B-PG9-Pad107)") (class "Default")
      (node (ref "U1") (pin "107") (pinfunction "PG9_107") (pintype "bidirectional"))
    )
    (net (code "178") (name "unconnected-(U1C-VBAT-Pad6)") (class "Default")
      (node (ref "U1") (pin "6") (pinfunction "VBAT_6") (pintype "power_in+no_connect"))
    )
    (net (code "179") (name "unconnected-(U2-NC-PadA3)") (class "Default")
      (node (ref "U2") (pin "A3") (pinfunction "NC_A3") (pintype "passive"))
    )
    (net (code "180") (name "unconnected-(U2-NC-PadC3)") (class "Default")
      (node (ref "U2") (pin "C3") (pinfunction "NC_C3") (pintype "passive"))
    )
  )
)
